# cambienmodbus.net
KiCad netlist of a schematic drawn in Altium Designer
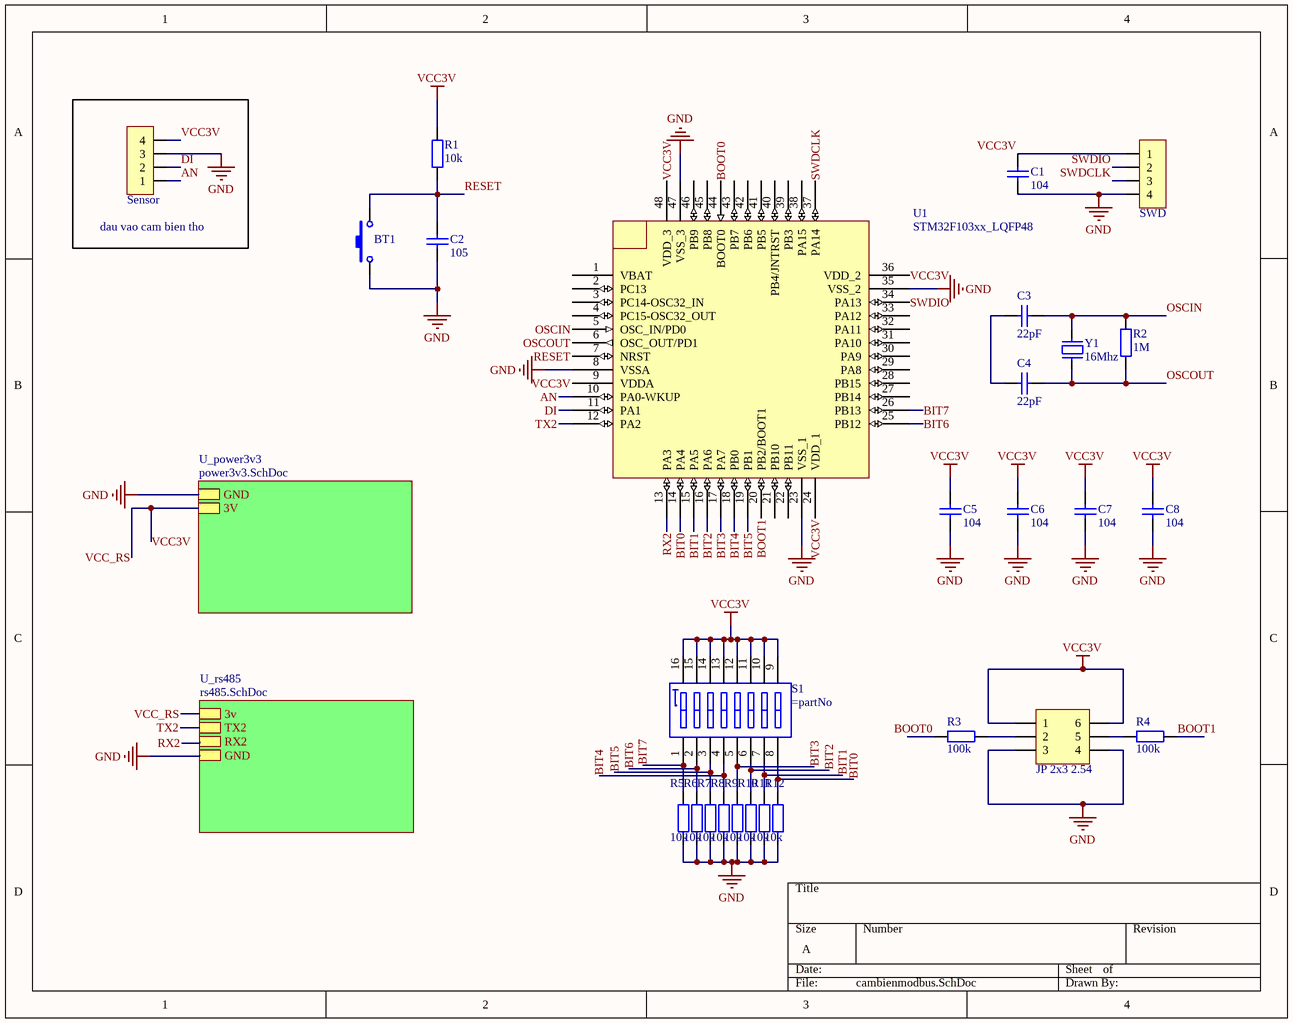
[diagram p0: cambienmodbus.SchDoc]

(export (version "E")
  (design (tool "Eeschema 10.0.6"))
  (components
    (comp (ref "BT1")
      (value "Nut Nhan 2 Chan SMD 3x6x2.5")
      (footprint "Nut Nhan 2 Chan SMD 3x6x2.5")
      (libsource (lib "Altium_Lib_by_KhueNguyenCreator") (part "Nut Nhan 2 Chan SMD 3x6x2.5"))
    )
    (comp (ref "C1")
      (value "104")
      (footprint "tu 0603")
      (description "Dán")
      (libsource (lib "Altium_Lib_by_KhueNguyenCreator") (part "Tu 0603 104 50V 10%"))
    )
    (comp (ref "C2")
      (value "105")
      (footprint "tu 0603")
      (description "Dán")
      (libsource (lib "Altium_Lib_by_KhueNguyenCreator") (part "Tu 0603 105 16V 20%"))
    )
    (comp (ref "C3")
      (value "22pF")
      (footprint "tu 0603")
      (description "Dán")
      (libsource (lib "Altium_Lib_by_KhueNguyenCreator") (part "Tu 0603 22pF 50V 10%"))
    )
    (comp (ref "C4")
      (value "22pF")
      (footprint "tu 0603")
      (description "Dán")
      (libsource (lib "Altium_Lib_by_KhueNguyenCreator") (part "Tu 0603 22pF 50V 10%"))
    )
    (comp (ref "C5")
      (value "104")
      (footprint "tu 0603")
      (description "Dán")
      (libsource (lib "Altium_Lib_by_KhueNguyenCreator") (part "Tu 0603 104 50V 10%"))
    )
    (comp (ref "C6")
      (value "104")
      (footprint "tu 0603")
      (description "Dán")
      (libsource (lib "Altium_Lib_by_KhueNguyenCreator") (part "Tu 0603 104 50V 10%"))
    )
    (comp (ref "C7")
      (value "104")
      (footprint "tu 0603")
      (description "Dán")
      (libsource (lib "Altium_Lib_by_KhueNguyenCreator") (part "Tu 0603 104 50V 10%"))
    )
    (comp (ref "C8")
      (value "104")
      (footprint "tu 0603")
      (description "Dán")
      (libsource (lib "Altium_Lib_by_KhueNguyenCreator") (part "Tu 0603 104 50V 10%"))
    )
    (comp (ref "JP1")
      (value "Sensor")
      (footprint "JP 1x4 CC")
      (description "Cắm")
      (libsource (lib "Altium_Lib_by_KhueNguyenCreator") (part "JP 1x4 2.54 Cai Cong"))
    )
    (comp (ref "JP2")
      (value "SWD")
      (footprint "JP 1x4 DT")
      (description "Cắm")
      (libsource (lib "Altium_Lib_by_KhueNguyenCreator") (part "JP 1x4 2.54 Duc Thang"))
    )
    (comp (ref "JP3")
      (value "JP 2x3 2.54")
      (footprint "JP 2x3 DT")
      (description "Cắm")
      (libsource (lib "Altium_Lib_by_KhueNguyenCreator") (part "JP 2x3 2.54 Duc Thang"))
    )
    (comp (ref "R1")
      (value "10k")
      (footprint "tro smd 0603")
      (description "Dán")
      (libsource (lib "Altium_Lib_by_KhueNguyenCreator") (part "Tro 0603 5% 10k"))
    )
    (comp (ref "R2")
      (value "1M")
      (footprint "tro smd 0603")
      (description "Dán")
      (libsource (lib "Altium_Lib_by_KhueNguyenCreator") (part "Tro 0603 5% 1M"))
    )
    (comp (ref "R3")
      (value "100k")
      (footprint "tro smd 0603")
      (description "Dán")
      (libsource (lib "Altium_Lib_by_KhueNguyenCreator") (part "Tro 0603 5% 100k"))
    )
    (comp (ref "R4")
      (value "100k")
      (footprint "tro smd 0603")
      (description "Dán")
      (libsource (lib "Altium_Lib_by_KhueNguyenCreator") (part "Tro 0603 5% 100k"))
    )
    (comp (ref "R5")
      (value "10k")
      (footprint "tro smd 0603")
      (description "Dán")
      (libsource (lib "Altium_Lib_by_KhueNguyenCreator") (part "Tro 0603 5% 10k"))
    )
    (comp (ref "R6")
      (value "10k")
      (footprint "tro smd 0603")
      (description "Dán")
      (libsource (lib "Altium_Lib_by_KhueNguyenCreator") (part "Tro 0603 5% 10k"))
    )
    (comp (ref "R7")
      (value "10k")
      (footprint "tro smd 0603")
      (description "Dán")
      (libsource (lib "Altium_Lib_by_KhueNguyenCreator") (part "Tro 0603 5% 10k"))
    )
    (comp (ref "R8")
      (value "10k")
      (footprint "tro smd 0603")
      (description "Dán")
      (libsource (lib "Altium_Lib_by_KhueNguyenCreator") (part "Tro 0603 5% 10k"))
    )
    (comp (ref "R9")
      (value "10k")
      (footprint "tro smd 0603")
      (description "Dán")
      (libsource (lib "Altium_Lib_by_KhueNguyenCreator") (part "Tro 0603 5% 10k"))
    )
    (comp (ref "R10")
      (value "10k")
      (footprint "tro smd 0603")
      (description "Dán")
      (libsource (lib "Altium_Lib_by_KhueNguyenCreator") (part "Tro 0603 5% 10k"))
    )
    (comp (ref "R11")
      (value "10k")
      (footprint "tro smd 0603")
      (description "Dán")
      (libsource (lib "Altium_Lib_by_KhueNguyenCreator") (part "Tro 0603 5% 10k"))
    )
    (comp (ref "R12")
      (value "10k")
      (footprint "tro smd 0603")
      (description "Dán")
      (libsource (lib "Altium_Lib_by_KhueNguyenCreator") (part "Tro 0603 5% 10k"))
    )
    (comp (ref "S1")
      (value "~")
      (footprint "SW-DIP8")
      (description "WS-DITV 2.54 mm small compact THT flat actuator with top tape")
      (fields
        (field (name "MANUFACTURER") "Wurth Elektronik")
        (field (name "PART NO.") "418127160908")
        (field (name "CREATED BY") "Baojun Chen")
      )
      (libsource (lib "LIBRARY1") (part "SWDIP8"))
    )
    (comp (ref "U1")
      (value "STM32F103xx_LQFP48")
      (footprint "STM32_LQPF48")
      (fields (field (name "PUBLISHER") "Altium Limited"))
      (libsource (lib "Altium_Lib_by_KhueNguyenCreator") (part "STM32F103xx_LQFP48"))
    )
    (comp (ref "Y1")
      (value "16Mhz")
      (footprint "Thach Anh 2 chan cam")
      (description "Crystal For all Crystal 2pin.")
      (libsource (lib "Altium_Lib_by_KhueNguyenCreator") (part "Thach Anh 2 chan Cam"))
    )
  )
  (nets
    (net (code "1") (name "/AN") (class "Default")
      (node (ref "JP1") (pin "1") (pinfunction "1_1") (pintype "passive"))
      (node (ref "U1") (pin "10") (pinfunction "PA0-WKUP_10") (pintype "bidirectional"))
    )
    (net (code "2") (name "/BIT0") (class "Default")
      (node (ref "R12") (pin "2") (pinfunction "2_2") (pintype "passive"))
      (node (ref "S1") (pin "8") (pinfunction "8_8") (pintype "passive"))
      (node (ref "U1") (pin "14") (pinfunction "PA4_14") (pintype "bidirectional"))
    )
    (net (code "3") (name "/BIT1") (class "Default")
      (node (ref "R11") (pin "2") (pinfunction "2_2") (pintype "passive"))
      (node (ref "S1") (pin "7") (pinfunction "7_7") (pintype "passive"))
      (node (ref "U1") (pin "15") (pinfunction "PA5_15") (pintype "bidirectional"))
    )
    (net (code "4") (name "/BIT2") (class "Default")
      (node (ref "R10") (pin "2") (pinfunction "2_2") (pintype "passive"))
      (node (ref "S1") (pin "6") (pinfunction "6_6") (pintype "passive"))
      (node (ref "U1") (pin "16") (pinfunction "PA6_16") (pintype "bidirectional"))
    )
    (net (code "5") (name "/BIT3") (class "Default")
      (node (ref "R9") (pin "2") (pinfunction "2_2") (pintype "passive"))
      (node (ref "S1") (pin "5") (pinfunction "5_5") (pintype "passive"))
      (node (ref "U1") (pin "17") (pinfunction "PA7_17") (pintype "bidirectional"))
    )
    (net (code "6") (name "/BIT4") (class "Default")
      (node (ref "R8") (pin "2") (pinfunction "2_2") (pintype "passive"))
      (node (ref "S1") (pin "4") (pinfunction "4_4") (pintype "passive"))
      (node (ref "U1") (pin "18") (pinfunction "PB0_18") (pintype "bidirectional"))
    )
    (net (code "7") (name "/BIT5") (class "Default")
      (node (ref "R7") (pin "2") (pinfunction "2_2") (pintype "passive"))
      (node (ref "S1") (pin "3") (pinfunction "3_3") (pintype "passive"))
      (node (ref "U1") (pin "19") (pinfunction "PB1_19") (pintype "bidirectional"))
    )
    (net (code "8") (name "/BIT6") (class "Default")
      (node (ref "R6") (pin "2") (pinfunction "2_2") (pintype "passive"))
      (node (ref "S1") (pin "2") (pinfunction "2_2") (pintype "passive"))
      (node (ref "U1") (pin "25") (pinfunction "PB12_25") (pintype "bidirectional"))
    )
    (net (code "9") (name "/BIT7") (class "Default")
      (node (ref "R5") (pin "2") (pinfunction "2_2") (pintype "passive"))
      (node (ref "S1") (pin "1") (pinfunction "1_1") (pintype "passive"))
      (node (ref "U1") (pin "26") (pinfunction "PB13_26") (pintype "bidirectional"))
    )
    (net (code "10") (name "/BOOT0") (class "Default")
      (node (ref "R3") (pin "1") (pinfunction "1_1") (pintype "passive"))
      (node (ref "U1") (pin "44") (pinfunction "BOOT0_44") (pintype "input"))
    )
    (net (code "11") (name "/BOOT1") (class "Default")
      (node (ref "R4") (pin "2") (pinfunction "2_2") (pintype "passive"))
      (node (ref "U1") (pin "20") (pinfunction "PB2/BOOT1_20") (pintype "bidirectional"))
    )
    (net (code "12") (name "/DI") (class "Default")
      (node (ref "JP1") (pin "2") (pinfunction "2_2") (pintype "passive"))
      (node (ref "U1") (pin "11") (pinfunction "PA1_11") (pintype "bidirectional"))
    )
    (net (code "13") (name "/OSCIN") (class "Default")
      (node (ref "C3") (pin "1") (pinfunction "1_1") (pintype "passive"))
      (node (ref "R2") (pin "2") (pinfunction "2_2") (pintype "passive"))
      (node (ref "U1") (pin "5") (pinfunction "OSC_IN/PD0_5") (pintype "input"))
      (node (ref "Y1") (pin "2") (pinfunction "2_2") (pintype "passive"))
    )
    (net (code "14") (name "/OSCOUT") (class "Default")
      (node (ref "C4") (pin "1") (pinfunction "1_1") (pintype "passive"))
      (node (ref "R2") (pin "1") (pinfunction "1_1") (pintype "passive"))
      (node (ref "U1") (pin "6") (pinfunction "OSC_OUT/PD1_6") (pintype "output"))
      (node (ref "Y1") (pin "1") (pinfunction "1_1") (pintype "passive"))
    )
    (net (code "15") (name "/RESET") (class "Default")
      (node (ref "BT1") (pin "2") (pinfunction "2_2") (pintype "passive"))
      (node (ref "C2") (pin "1") (pinfunction "1_1") (pintype "passive"))
      (node (ref "R1") (pin "1") (pinfunction "1_1") (pintype "passive"))
      (node (ref "U1") (pin "7") (pinfunction "NRST_7") (pintype "bidirectional"))
    )
    (net (code "16") (name "/RX2") (class "Default")
      (node (ref "U1") (pin "13") (pinfunction "PA3_13") (pintype "bidirectional"))
    )
    (net (code "17") (name "/SWDCLK") (class "Default")
      (node (ref "JP2") (pin "3") (pinfunction "3_3") (pintype "passive"))
      (node (ref "U1") (pin "37") (pinfunction "PA14_37") (pintype "bidirectional"))
    )
    (net (code "18") (name "/SWDIO") (class "Default")
      (node (ref "JP2") (pin "2") (pinfunction "2_2") (pintype "passive"))
      (node (ref "U1") (pin "34") (pinfunction "PA13_34") (pintype "bidirectional"))
    )
    (net (code "19") (name "/TX2") (class "Default")
      (node (ref "U1") (pin "12") (pinfunction "PA2_12") (pintype "bidirectional"))
    )
    (net (code "20") (name "GND") (class "Default")
      (node (ref "BT1") (pin "1") (pinfunction "1_1") (pintype "passive"))
      (node (ref "C1") (pin "2") (pinfunction "2_2") (pintype "passive"))
      (node (ref "C2") (pin "2") (pinfunction "2_2") (pintype "passive"))
      (node (ref "C5") (pin "2") (pinfunction "2_2") (pintype "passive"))
      (node (ref "C6") (pin "2") (pinfunction "2_2") (pintype "passive"))
      (node (ref "C7") (pin "2") (pinfunction "2_2") (pintype "passive"))
      (node (ref "C8") (pin "2") (pinfunction "2_2") (pintype "passive"))
      (node (ref "JP1") (pin "3") (pinfunction "3_3") (pintype "passive"))
      (node (ref "JP2") (pin "4") (pinfunction "4_4") (pintype "passive"))
      (node (ref "JP3") (pin "3") (pinfunction "3_3") (pintype "passive"))
      (node (ref "JP3") (pin "4") (pinfunction "4_4") (pintype "passive"))
      (node (ref "R10") (pin "1") (pinfunction "1_1") (pintype "passive"))
      (node (ref "R11") (pin "1") (pinfunction "1_1") (pintype "passive"))
      (node (ref "R12") (pin "1") (pinfunction "1_1") (pintype "passive"))
      (node (ref "R5") (pin "1") (pinfunction "1_1") (pintype "passive"))
      (node (ref "R6") (pin "1") (pinfunction "1_1") (pintype "passive"))
      (node (ref "R7") (pin "1") (pinfunction "1_1") (pintype "passive"))
      (node (ref "R8") (pin "1") (pinfunction "1_1") (pintype "passive"))
      (node (ref "R9") (pin "1") (pinfunction "1_1") (pintype "passive"))
      (node (ref "U1") (pin "23") (pinfunction "VSS_1_23") (pintype "power_in"))
      (node (ref "U1") (pin "35") (pinfunction "VSS_2_35") (pintype "power_in"))
      (node (ref "U1") (pin "47") (pinfunction "VSS_3_47") (pintype "power_in"))
      (node (ref "U1") (pin "8") (pinfunction "VSSA_8") (pintype "power_in"))
    )
    (net (code "21") (name "Net-(C3-Pad2)") (class "Default")
      (node (ref "C3") (pin "2") (pinfunction "2_2") (pintype "passive"))
      (node (ref "C4") (pin "2") (pinfunction "2_2") (pintype "passive"))
    )
    (net (code "22") (name "Net-(JP3-Pad2)") (class "Default")
      (node (ref "JP3") (pin "2") (pinfunction "2_2") (pintype "passive"))
      (node (ref "R3") (pin "2") (pinfunction "2_2") (pintype "passive"))
    )
    (net (code "23") (name "Net-(JP3-Pad5)") (class "Default")
      (node (ref "JP3") (pin "5") (pinfunction "5_5") (pintype "passive"))
      (node (ref "R4") (pin "1") (pinfunction "1_1") (pintype "passive"))
    )
    (net (code "24") (name "VCC3V") (class "Default")
      (node (ref "C1") (pin "1") (pinfunction "1_1") (pintype "passive"))
      (node (ref "C5") (pin "1") (pinfunction "1_1") (pintype "passive"))
      (node (ref "C6") (pin "1") (pinfunction "1_1") (pintype "passive"))
      (node (ref "C7") (pin "1") (pinfunction "1_1") (pintype "passive"))
      (node (ref "C8") (pin "1") (pinfunction "1_1") (pintype "passive"))
      (node (ref "JP1") (pin "4") (pinfunction "4_4") (pintype "passive"))
      (node (ref "JP2") (pin "1") (pinfunction "1_1") (pintype "passive"))
      (node (ref "JP3") (pin "1") (pinfunction "1_1") (pintype "passive"))
      (node (ref "JP3") (pin "6") (pinfunction "6_6") (pintype "passive"))
      (node (ref "R1") (pin "2") (pinfunction "2_2") (pintype "passive"))
      (node (ref "S1") (pin "10") (pinfunction "10_10") (pintype "passive"))
      (node (ref "S1") (pin "11") (pinfunction "11_11") (pintype "passive"))
      (node (ref "S1") (pin "12") (pinfunction "12_12") (pintype "passive"))
      (node (ref "S1") (pin "13") (pinfunction "13_13") (pintype "passive"))
      (node (ref "S1") (pin "14") (pinfunction "14_14") (pintype "passive"))
      (node (ref "S1") (pin "15") (pinfunction "15_15") (pintype "passive"))
      (node (ref "S1") (pin "16") (pinfunction "16_16") (pintype "passive"))
      (node (ref "S1") (pin "9") (pinfunction "9_9") (pintype "passive"))
      (node (ref "U1") (pin "24") (pinfunction "VDD_1_24") (pintype "power_in"))
      (node (ref "U1") (pin "36") (pinfunction "VDD_2_36") (pintype "power_in"))
      (node (ref "U1") (pin "48") (pinfunction "VDD_3_48") (pintype "power_in"))
      (node (ref "U1") (pin "9") (pinfunction "VDDA_9") (pintype "power_in"))
    )
    (net (code "25") (name "unconnected-(U1-PA8-Pad29)") (class "Default")
      (node (ref "U1") (pin "29") (pinfunction "PA8_29") (pintype "bidirectional"))
    )
    (net (code "26") (name "unconnected-(U1-PA9-Pad30)") (class "Default")
      (node (ref "U1") (pin "30") (pinfunction "PA9_30") (pintype "bidirectional"))
    )
    (net (code "27") (name "unconnected-(U1-PA10-Pad31)") (class "Default")
      (node (ref "U1") (pin "31") (pinfunction "PA10_31") (pintype "bidirectional"))
    )
    (net (code "28") (name "unconnected-(U1-PA11-Pad32)") (class "Default")
      (node (ref "U1") (pin "32") (pinfunction "PA11_32") (pintype "bidirectional"))
    )
    (net (code "29") (name "unconnected-(U1-PA12-Pad33)") (class "Default")
      (node (ref "U1") (pin "33") (pinfunction "PA12_33") (pintype "bidirectional"))
    )
    (net (code "30") (name "unconnected-(U1-PA15-Pad38)") (class "Default")
      (node (ref "U1") (pin "38") (pinfunction "PA15_38") (pintype "bidirectional"))
    )
    (net (code "31") (name "unconnected-(U1-PB3-Pad39)") (class "Default")
      (node (ref "U1") (pin "39") (pinfunction "PB3_39") (pintype "bidirectional"))
    )
    (net (code "32") (name "unconnected-(U1-PB4{slash}JNTRST-Pad40)") (class "Default")
      (node (ref "U1") (pin "40") (pinfunction "PB4/JNTRST_40") (pintype "bidirectional"))
    )
    (net (code "33") (name "unconnected-(U1-PB5-Pad41)") (class "Default")
      (node (ref "U1") (pin "41") (pinfunction "PB5_41") (pintype "bidirectional"))
    )
    (net (code "34") (name "unconnected-(U1-PB6-Pad42)") (class "Default")
      (node (ref "U1") (pin "42") (pinfunction "PB6_42") (pintype "bidirectional"))
    )
    (net (code "35") (name "unconnected-(U1-PB7-Pad43)") (class "Default")
      (node (ref "U1") (pin "43") (pinfunction "PB7_43") (pintype "bidirectional"))
    )
    (net (code "36") (name "unconnected-(U1-PB8-Pad45)") (class "Default")
      (node (ref "U1") (pin "45") (pinfunction "PB8_45") (pintype "bidirectional"))
    )
    (net (code "37") (name "unconnected-(U1-PB9-Pad46)") (class "Default")
      (node (ref "U1") (pin "46") (pinfunction "PB9_46") (pintype "bidirectional"))
    )
    (net (code "38") (name "unconnected-(U1-PB10-Pad21)") (class "Default")
      (node (ref "U1") (pin "21") (pinfunction "PB10_21") (pintype "bidirectional"))
    )
    (net (code "39") (name "unconnected-(U1-PB11-Pad22)") (class "Default")
      (node (ref "U1") (pin "22") (pinfunction "PB11_22") (pintype "bidirectional"))
    )
    (net (code "40") (name "unconnected-(U1-PB14-Pad27)") (class "Default")
      (node (ref "U1") (pin "27") (pinfunction "PB14_27") (pintype "bidirectional"))
    )
    (net (code "41") (name "unconnected-(U1-PB15-Pad28)") (class "Default")
      (node (ref "U1") (pin "28") (pinfunction "PB15_28") (pintype "bidirectional"))
    )
    (net (code "42") (name "unconnected-(U1-PC13-Pad2)") (class "Default")
      (node (ref "U1") (pin "2") (pinfunction "PC13_2") (pintype "bidirectional"))
    )
    (net (code "43") (name "unconnected-(U1-PC14-OSC32_IN-Pad3)") (class "Default")
      (node (ref "U1") (pin "3") (pinfunction "PC14-OSC32_IN_3") (pintype "bidirectional"))
    )
    (net (code "44") (name "unconnected-(U1-PC15-OSC32_OUT-Pad4)") (class "Default")
      (node (ref "U1") (pin "4") (pinfunction "PC15-OSC32_OUT_4") (pintype "bidirectional"))
    )
    (net (code "45") (name "unconnected-(U1-VBAT-Pad1)") (class "Default")
      (node (ref "U1") (pin "1") (pinfunction "VBAT_1") (pintype "power_in"))
    )
  )
)
